# MouseGoggles_Hat-1-5.net
KiCad netlist of a schematic drawn in EAGLE
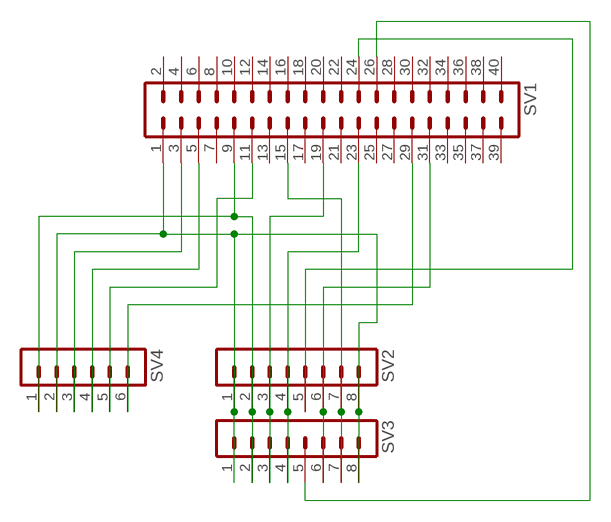
[diagram p0: schematic, sheet 1]

(export (version "E")
  (design (tool "Eeschema 10.0.6"))
  (components
    (comp (ref "SV1")
      (value "MA20-2")
      (footprint "eagle-import:MA20-2")
      (libsource (lib "eagle-import") (part "MA20-2"))
    )
    (comp (ref "SV2")
      (value "MA08-1")
      (footprint "eagle-import:MA08-1")
      (libsource (lib "eagle-import") (part "MA08-1"))
    )
    (comp (ref "SV3")
      (value "MA08-1")
      (footprint "eagle-import:MA08-1")
      (libsource (lib "eagle-import") (part "MA08-1"))
    )
    (comp (ref "SV4")
      (value "MA06-1")
      (footprint "eagle-import:MA06-1")
      (libsource (lib "eagle-import") (part "MA06-1"))
    )
  )
  (nets
    (net (code "1") (name "Net-(SV1-Pad1)") (class "Default")
      (node (ref "SV1") (pin "1") (pinfunction "1_1") (pintype "passive"))
      (node (ref "SV2") (pin "1") (pinfunction "1_1") (pintype "passive"))
      (node (ref "SV2") (pin "8") (pinfunction "8_8") (pintype "passive"))
      (node (ref "SV3") (pin "1") (pinfunction "1_1") (pintype "passive"))
      (node (ref "SV3") (pin "8") (pinfunction "8_8") (pintype "passive"))
      (node (ref "SV4") (pin "2") (pinfunction "2_2") (pintype "passive"))
    )
    (net (code "2") (name "Net-(SV1-Pad3)") (class "Default")
      (node (ref "SV1") (pin "3") (pinfunction "3_3") (pintype "passive"))
      (node (ref "SV4") (pin "3") (pinfunction "3_3") (pintype "passive"))
    )
    (net (code "3") (name "Net-(SV1-Pad5)") (class "Default")
      (node (ref "SV1") (pin "5") (pinfunction "5_5") (pintype "passive"))
      (node (ref "SV4") (pin "4") (pinfunction "4_4") (pintype "passive"))
    )
    (net (code "4") (name "Net-(SV1-Pad9)") (class "Default")
      (node (ref "SV1") (pin "9") (pinfunction "9_9") (pintype "passive"))
      (node (ref "SV2") (pin "2") (pinfunction "2_2") (pintype "passive"))
      (node (ref "SV3") (pin "2") (pinfunction "2_2") (pintype "passive"))
      (node (ref "SV4") (pin "1") (pinfunction "1_1") (pintype "passive"))
    )
    (net (code "5") (name "Net-(SV1-Pad11)") (class "Default")
      (node (ref "SV1") (pin "11") (pinfunction "11_11") (pintype "passive"))
      (node (ref "SV4") (pin "5") (pinfunction "5_5") (pintype "passive"))
    )
    (net (code "6") (name "Net-(SV1-Pad15)") (class "Default")
      (node (ref "SV1") (pin "15") (pinfunction "15_15") (pintype "passive"))
      (node (ref "SV2") (pin "7") (pinfunction "7_7") (pintype "passive"))
      (node (ref "SV3") (pin "7") (pinfunction "7_7") (pintype "passive"))
    )
    (net (code "7") (name "Net-(SV1-Pad19)") (class "Default")
      (node (ref "SV1") (pin "19") (pinfunction "19_19") (pintype "passive"))
      (node (ref "SV2") (pin "3") (pinfunction "3_3") (pintype "passive"))
      (node (ref "SV3") (pin "3") (pinfunction "3_3") (pintype "passive"))
    )
    (net (code "8") (name "Net-(SV1-Pad23)") (class "Default")
      (node (ref "SV1") (pin "23") (pinfunction "23_23") (pintype "passive"))
      (node (ref "SV2") (pin "4") (pinfunction "4_4") (pintype "passive"))
      (node (ref "SV3") (pin "4") (pinfunction "4_4") (pintype "passive"))
    )
    (net (code "9") (name "Net-(SV1-Pad24)") (class "Default")
      (node (ref "SV1") (pin "24") (pinfunction "24_24") (pintype "passive"))
      (node (ref "SV2") (pin "5") (pinfunction "5_5") (pintype "passive"))
    )
    (net (code "10") (name "Net-(SV1-Pad26)") (class "Default")
      (node (ref "SV1") (pin "26") (pinfunction "26_26") (pintype "passive"))
      (node (ref "SV3") (pin "5") (pinfunction "5_5") (pintype "passive"))
    )
    (net (code "11") (name "Net-(SV1-Pad29)") (class "Default")
      (node (ref "SV1") (pin "29") (pinfunction "29_29") (pintype "passive"))
      (node (ref "SV4") (pin "6") (pinfunction "6_6") (pintype "passive"))
    )
    (net (code "12") (name "Net-(SV1-Pad31)") (class "Default")
      (node (ref "SV1") (pin "31") (pinfunction "31_31") (pintype "passive"))
      (node (ref "SV2") (pin "6") (pinfunction "6_6") (pintype "passive"))
      (node (ref "SV3") (pin "6") (pinfunction "6_6") (pintype "passive"))
    )
    (net (code "13") (name "unconnected-(SV1-Pad2)") (class "Default")
      (node (ref "SV1") (pin "2") (pinfunction "2_2") (pintype "passive"))
    )
    (net (code "14") (name "unconnected-(SV1-Pad4)") (class "Default")
      (node (ref "SV1") (pin "4") (pinfunction "4_4") (pintype "passive"))
    )
    (net (code "15") (name "unconnected-(SV1-Pad6)") (class "Default")
      (node (ref "SV1") (pin "6") (pinfunction "6_6") (pintype "passive"))
    )
    (net (code "16") (name "unconnected-(SV1-Pad7)") (class "Default")
      (node (ref "SV1") (pin "7") (pinfunction "7_7") (pintype "passive"))
    )
    (net (code "17") (name "unconnected-(SV1-Pad8)") (class "Default")
      (node (ref "SV1") (pin "8") (pinfunction "8_8") (pintype "passive"))
    )
    (net (code "18") (name "unconnected-(SV1-Pad10)") (class "Default")
      (node (ref "SV1") (pin "10") (pinfunction "10_10") (pintype "passive"))
    )
    (net (code "19") (name "unconnected-(SV1-Pad12)") (class "Default")
      (node (ref "SV1") (pin "12") (pinfunction "12_12") (pintype "passive"))
    )
    (net (code "20") (name "unconnected-(SV1-Pad13)") (class "Default")
      (node (ref "SV1") (pin "13") (pinfunction "13_13") (pintype "passive"))
    )
    (net (code "21") (name "unconnected-(SV1-Pad14)") (class "Default")
      (node (ref "SV1") (pin "14") (pinfunction "14_14") (pintype "passive"))
    )
    (net (code "22") (name "unconnected-(SV1-Pad16)") (class "Default")
      (node (ref "SV1") (pin "16") (pinfunction "16_16") (pintype "passive"))
    )
    (net (code "23") (name "unconnected-(SV1-Pad17)") (class "Default")
      (node (ref "SV1") (pin "17") (pinfunction "17_17") (pintype "passive"))
    )
    (net (code "24") (name "unconnected-(SV1-Pad18)") (class "Default")
      (node (ref "SV1") (pin "18") (pinfunction "18_18") (pintype "passive"))
    )
    (net (code "25") (name "unconnected-(SV1-Pad20)") (class "Default")
      (node (ref "SV1") (pin "20") (pinfunction "20_20") (pintype "passive"))
    )
    (net (code "26") (name "unconnected-(SV1-Pad21)") (class "Default")
      (node (ref "SV1") (pin "21") (pinfunction "21_21") (pintype "passive"))
    )
    (net (code "27") (name "unconnected-(SV1-Pad22)") (class "Default")
      (node (ref "SV1") (pin "22") (pinfunction "22_22") (pintype "passive"))
    )
    (net (code "28") (name "unconnected-(SV1-Pad25)") (class "Default")
      (node (ref "SV1") (pin "25") (pinfunction "25_25") (pintype "passive"))
    )
    (net (code "29") (name "unconnected-(SV1-Pad27)") (class "Default")
      (node (ref "SV1") (pin "27") (pinfunction "27_27") (pintype "passive"))
    )
    (net (code "30") (name "unconnected-(SV1-Pad28)") (class "Default")
      (node (ref "SV1") (pin "28") (pinfunction "28_28") (pintype "passive"))
    )
    (net (code "31") (name "unconnected-(SV1-Pad30)") (class "Default")
      (node (ref "SV1") (pin "30") (pinfunction "30_30") (pintype "passive"))
    )
    (net (code "32") (name "unconnected-(SV1-Pad32)") (class "Default")
      (node (ref "SV1") (pin "32") (pinfunction "32_32") (pintype "passive"))
    )
    (net (code "33") (name "unconnected-(SV1-Pad33)") (class "Default")
      (node (ref "SV1") (pin "33") (pinfunction "33_33") (pintype "passive"))
    )
    (net (code "34") (name "unconnected-(SV1-Pad34)") (class "Default")
      (node (ref "SV1") (pin "34") (pinfunction "34_34") (pintype "passive"))
    )
    (net (code "35") (name "unconnected-(SV1-Pad35)") (class "Default")
      (node (ref "SV1") (pin "35") (pinfunction "35_35") (pintype "passive"))
    )
    (net (code "36") (name "unconnected-(SV1-Pad36)") (class "Default")
      (node (ref "SV1") (pin "36") (pinfunction "36_36") (pintype "passive"))
    )
    (net (code "37") (name "unconnected-(SV1-Pad37)") (class "Default")
      (node (ref "SV1") (pin "37") (pinfunction "37_37") (pintype "passive"))
    )
    (net (code "38") (name "unconnected-(SV1-Pad38)") (class "Default")
      (node (ref "SV1") (pin "38") (pinfunction "38_38") (pintype "passive"))
    )
    (net (code "39") (name "unconnected-(SV1-Pad39)") (class "Default")
      (node (ref "SV1") (pin "39") (pinfunction "39_39") (pintype "passive"))
    )
    (net (code "40") (name "unconnected-(SV1-Pad40)") (class "Default")
      (node (ref "SV1") (pin "40") (pinfunction "40_40") (pintype "passive"))
    )
  )
)
